# alphanumeric.net
KiCad netlist of a schematic drawn in Altium Designer
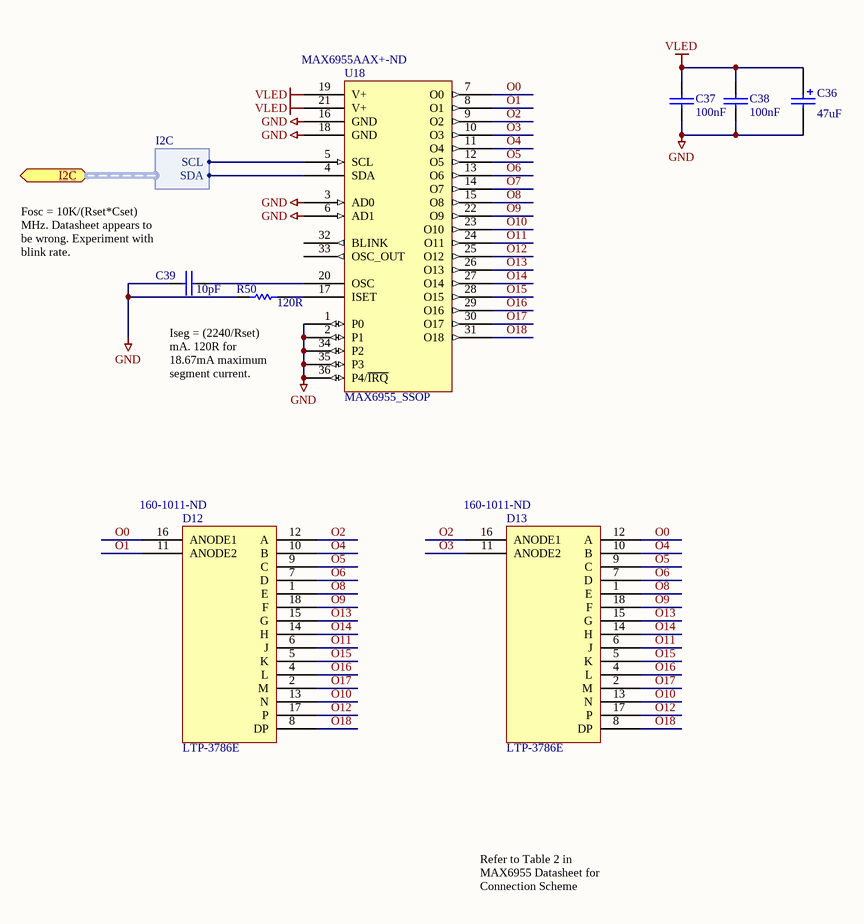
[diagram p0: alphanumeric.SchDoc]

(export (version "E")
  (design (tool "Eeschema 10.0.6"))
  (components
    (comp (ref "C36")
      (value "47uF")
      (footprint "CAPMP7343X19N (Murata D4)")
      (description "Polarized Capacitor (Surface Mount)")
      (fields
        (field (name "MANUFACTURER") "Generic Components")
        (field (name "MANUFACTURER PART NUMBER") "ECASD40J476M025K00")
        (field (name "PUBLISHER") "Altium Limited")
      )
      (libsource (lib "RCLDQ") (part "CAP POL3"))
    )
    (comp (ref "C37")
      (value "100nF")
      (footprint "0603")
      (description "Capacitor")
      (fields
        (field (name "MANUFACTURER") "TDK Corporation")
        (field (name "MANUFACTURER PART NUMBER") "C1608X7R1H103K080AA")
      )
      (libsource (lib "*") (part "CAP"))
    )
    (comp (ref "C38")
      (value "100nF")
      (footprint "0603")
      (description "Capacitor")
      (fields
        (field (name "MANUFACTURER") "TDK Corporation")
        (field (name "MANUFACTURER PART NUMBER") "C1608X7R1H103K080AA")
      )
      (libsource (lib "*") (part "CAP"))
    )
    (comp (ref "C39")
      (value "10pF")
      (footprint "0603")
      (description "Capacitor")
      (fields
        (field (name "MANUFACTURER") "TDK Corporation")
        (field (name "MANUFACTURER PART NUMBER") "C1608C0G1H100D080AA")
      )
      (libsource (lib "*") (part "CAP"))
    )
    (comp (ref "D12")
      (value "LTP-3786E")
      (footprint "LTP-3786E")
      (description "LED ALPHNUM.54\" 2DGT RED-ORNG CA")
      (fields
        (field (name "SUPPLIER PART NUMBER 1") "160-1011-ND")
        (field (name "MANUFACTURER") "Lite-On Inc")
      )
      (libsource (lib "steve") (part "LTP-3786E"))
    )
    (comp (ref "D13")
      (value "LTP-3786E")
      (footprint "LTP-3786E")
      (description "LED ALPHNUM.54\" 2DGT RED-ORNG CA")
      (fields
        (field (name "SUPPLIER PART NUMBER 1") "160-1011-ND")
        (field (name "MANUFACTURER") "Lite-On Inc")
      )
      (libsource (lib "steve") (part "LTP-3786E"))
    )
    (comp (ref "R50")
      (value "120R")
      (footprint "0603")
      (description "Semiconductor Resistor")
      (fields
        (field (name "MANUFACTURER") "Panasonic Electronic Components")
        (field (name "MANUFACTURER PART NUMBER") "ERJ-3EKF1200V")
        (field (name "PUBLISHER") "Altium Limited")
      )
      (libsource (lib "Miscellaneous Devices") (part "Res Semi"))
    )
    (comp (ref "U18")
      (value "MAX6955_SSOP")
      (footprint "SOP127P600-8N-36")
      (description "2-Wire Interfaced, 2.7V to 5.5V LED Display Driver")
      (fields
        (field (name "SUPPLIER PART NUMBER 1") "MAX6955AAX+-ND")
        (field (name "MANUFACTURER") "Maxim Integrated")
        (field (name "MANUFACTURER PART NUMBER") "MAX6955AAX+")
      )
      (libsource (lib "steve") (part "MAX6955_SSOP"))
    )
  )
  (nets
    (net (code "2") (name "/O0") (class "Default")
      (node (ref "D12") (pin "16") (pinfunction "ANODE1_16") (pintype "passive"))
      (node (ref "D13") (pin "12") (pinfunction "A_12") (pintype "passive"))
      (node (ref "U18") (pin "7") (pinfunction "O0_7") (pintype "output"))
    )
    (net (code "3") (name "/O1") (class "Default")
      (node (ref "D12") (pin "11") (pinfunction "ANODE2_11") (pintype "passive"))
      (node (ref "U18") (pin "8") (pinfunction "O1_8") (pintype "output"))
    )
    (net (code "4") (name "/O2") (class "Default")
      (node (ref "D12") (pin "12") (pinfunction "A_12") (pintype "passive"))
      (node (ref "D13") (pin "16") (pinfunction "ANODE1_16") (pintype "passive"))
      (node (ref "U18") (pin "9") (pinfunction "O2_9") (pintype "output"))
    )
    (net (code "5") (name "/O3") (class "Default")
      (node (ref "D13") (pin "11") (pinfunction "ANODE2_11") (pintype "passive"))
      (node (ref "U18") (pin "10") (pinfunction "O3_10") (pintype "output"))
    )
    (net (code "6") (name "/O4") (class "Default")
      (node (ref "D12") (pin "10") (pinfunction "B_10") (pintype "passive"))
      (node (ref "D13") (pin "10") (pinfunction "B_10") (pintype "passive"))
      (node (ref "U18") (pin "11") (pinfunction "O4_11") (pintype "output"))
    )
    (net (code "7") (name "/O5") (class "Default")
      (node (ref "D12") (pin "9") (pinfunction "C_9") (pintype "passive"))
      (node (ref "D13") (pin "9") (pinfunction "C_9") (pintype "passive"))
      (node (ref "U18") (pin "12") (pinfunction "O5_12") (pintype "output"))
    )
    (net (code "8") (name "/O6") (class "Default")
      (node (ref "D12") (pin "7") (pinfunction "D_7") (pintype "passive"))
      (node (ref "D13") (pin "7") (pinfunction "D_7") (pintype "passive"))
      (node (ref "U18") (pin "13") (pinfunction "O6_13") (pintype "output"))
    )
    (net (code "9") (name "/O7") (class "Default")
      (node (ref "U18") (pin "14") (pinfunction "O7_14") (pintype "output"))
    )
    (net (code "10") (name "/O8") (class "Default")
      (node (ref "D12") (pin "1") (pinfunction "E_1") (pintype "passive"))
      (node (ref "D13") (pin "1") (pinfunction "E_1") (pintype "passive"))
      (node (ref "U18") (pin "15") (pinfunction "O8_15") (pintype "output"))
    )
    (net (code "11") (name "/O9") (class "Default")
      (node (ref "D12") (pin "18") (pinfunction "F_18") (pintype "passive"))
      (node (ref "D13") (pin "18") (pinfunction "F_18") (pintype "passive"))
      (node (ref "U18") (pin "22") (pinfunction "O9_22") (pintype "output"))
    )
    (net (code "12") (name "/O10") (class "Default")
      (node (ref "D12") (pin "13") (pinfunction "N_13") (pintype "passive"))
      (node (ref "D13") (pin "13") (pinfunction "N_13") (pintype "passive"))
      (node (ref "U18") (pin "23") (pinfunction "O10_23") (pintype "output"))
    )
    (net (code "13") (name "/O11") (class "Default")
      (node (ref "D12") (pin "6") (pinfunction "J_6") (pintype "passive"))
      (node (ref "D13") (pin "6") (pinfunction "J_6") (pintype "passive"))
      (node (ref "U18") (pin "24") (pinfunction "O11_24") (pintype "output"))
    )
    (net (code "14") (name "/O12") (class "Default")
      (node (ref "D12") (pin "17") (pinfunction "P_17") (pintype "passive"))
      (node (ref "D13") (pin "17") (pinfunction "P_17") (pintype "passive"))
      (node (ref "U18") (pin "25") (pinfunction "O12_25") (pintype "output"))
    )
    (net (code "15") (name "/O13") (class "Default")
      (node (ref "D12") (pin "15") (pinfunction "G_15") (pintype "passive"))
      (node (ref "D13") (pin "15") (pinfunction "G_15") (pintype "passive"))
      (node (ref "U18") (pin "26") (pinfunction "O13_26") (pintype "output"))
    )
    (net (code "16") (name "/O14") (class "Default")
      (node (ref "D12") (pin "14") (pinfunction "H_14") (pintype "passive"))
      (node (ref "D13") (pin "14") (pinfunction "H_14") (pintype "passive"))
      (node (ref "U18") (pin "27") (pinfunction "O14_27") (pintype "output"))
    )
    (net (code "17") (name "/O15") (class "Default")
      (node (ref "D12") (pin "5") (pinfunction "K_5") (pintype "passive"))
      (node (ref "D13") (pin "5") (pinfunction "K_5") (pintype "passive"))
      (node (ref "U18") (pin "28") (pinfunction "O15_28") (pintype "output"))
    )
    (net (code "18") (name "/O16") (class "Default")
      (node (ref "D12") (pin "4") (pinfunction "L_4") (pintype "passive"))
      (node (ref "D13") (pin "4") (pinfunction "L_4") (pintype "passive"))
      (node (ref "U18") (pin "29") (pinfunction "O16_29") (pintype "output"))
    )
    (net (code "19") (name "/O17") (class "Default")
      (node (ref "D12") (pin "2") (pinfunction "M_2") (pintype "passive"))
      (node (ref "D13") (pin "2") (pinfunction "M_2") (pintype "passive"))
      (node (ref "U18") (pin "30") (pinfunction "O17_30") (pintype "output"))
    )
    (net (code "20") (name "/O18") (class "Default")
      (node (ref "D12") (pin "8") (pinfunction "DP_8") (pintype "passive"))
      (node (ref "D13") (pin "8") (pinfunction "DP_8") (pintype "passive"))
      (node (ref "U18") (pin "31") (pinfunction "O18_31") (pintype "output"))
    )
    (net (code "21") (name "/SCL") (class "Default")
      (node (ref "U18") (pin "5") (pinfunction "SCL_5") (pintype "input"))
    )
    (net (code "22") (name "/SDA") (class "Default")
      (node (ref "U18") (pin "4") (pinfunction "SDA_4") (pintype "open_collector"))
    )
    (net (code "24") (name "GND") (class "Default")
      (node (ref "C36") (pin "2") (pinfunction "2_2") (pintype "passive"))
      (node (ref "C37") (pin "1") (pinfunction "1_1") (pintype "passive"))
      (node (ref "C38") (pin "2") (pinfunction "2_2") (pintype "passive"))
      (node (ref "C39") (pin "1") (pinfunction "1_1") (pintype "passive"))
      (node (ref "R50") (pin "2") (pinfunction "2_2") (pintype "passive"))
      (node (ref "U18") (pin "1") (pinfunction "P0_1") (pintype "bidirectional"))
      (node (ref "U18") (pin "16") (pinfunction "GND_16") (pintype "power_in"))
      (node (ref "U18") (pin "18") (pinfunction "GND_18") (pintype "power_in"))
      (node (ref "U18") (pin "2") (pinfunction "P1_2") (pintype "bidirectional"))
      (node (ref "U18") (pin "3") (pinfunction "AD0_3") (pintype "input"))
      (node (ref "U18") (pin "34") (pinfunction "P2_34") (pintype "bidirectional"))
      (node (ref "U18") (pin "35") (pinfunction "P3_35") (pintype "bidirectional"))
      (node (ref "U18") (pin "36") (pinfunction "P4/~{IRQ}_36") (pintype "bidirectional"))
      (node (ref "U18") (pin "6") (pinfunction "AD1_6") (pintype "input"))
    )
    (net (code "25") (name "Net-(U18-ISET)") (class "Default")
      (node (ref "R50") (pin "1") (pinfunction "1_1") (pintype "passive"))
      (node (ref "U18") (pin "17") (pinfunction "ISET_17") (pintype "passive"))
    )
    (net (code "26") (name "Net-(U18-OSC)") (class "Default")
      (node (ref "C39") (pin "2") (pinfunction "2_2") (pintype "passive"))
      (node (ref "U18") (pin "20") (pinfunction "OSC_20") (pintype "passive"))
    )
    (net (code "27") (name "VLED") (class "Default")
      (node (ref "C36") (pin "1") (pinfunction "1_1") (pintype "passive"))
      (node (ref "C37") (pin "2") (pinfunction "2_2") (pintype "passive"))
      (node (ref "C38") (pin "1") (pinfunction "1_1") (pintype "passive"))
      (node (ref "U18") (pin "19") (pinfunction "V+_19") (pintype "power_in"))
      (node (ref "U18") (pin "21") (pinfunction "V+_21") (pintype "power_in"))
    )
    (net (code "28") (name "unconnected-(U18-BLINK-Pad32)") (class "Default")
      (node (ref "U18") (pin "32") (pinfunction "BLINK_32") (pintype "output"))
    )
    (net (code "29") (name "unconnected-(U18-OSC_OUT-Pad33)") (class "Default")
      (node (ref "U18") (pin "33") (pinfunction "OSC_OUT_33") (pintype "output"))
    )
  )
)
